# rpi-sstv.net
KiCad netlist of a schematic drawn in EAGLE
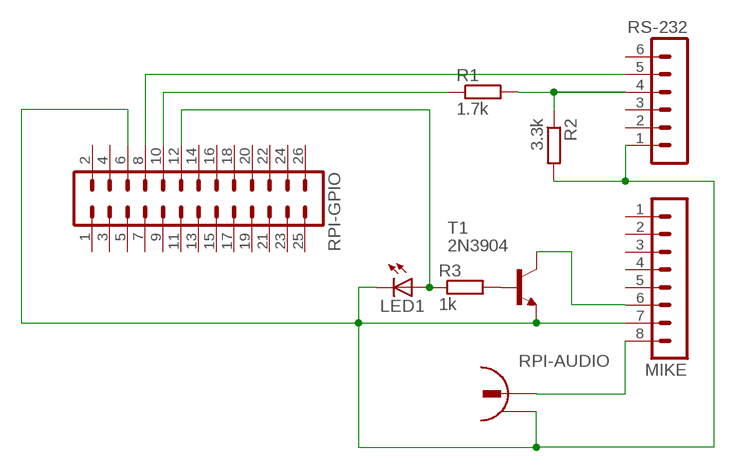
[diagram p0: schematic, sheet 1]

(export (version "E")
  (design (tool "Eeschema 10.0.6"))
  (components
    (comp (ref "LED1")
      (value "LED5MM")
      (footprint "eagle-import:LED5MM")
      (libsource (lib "eagle-import") (part "LED5MM"))
    )
    (comp (ref "MIKE")
      (value "MA08-1")
      (footprint "eagle-import:MA08-1")
      (libsource (lib "eagle-import") (part "MA08-1"))
    )
    (comp (ref "R1")
      (value "1.7k")
      (footprint "eagle-import:0411_15")
      (libsource (lib "eagle-import") (part "R-EU_0411/15"))
    )
    (comp (ref "R2")
      (value "3.3k")
      (footprint "eagle-import:0411_15")
      (libsource (lib "eagle-import") (part "R-EU_0411/15"))
    )
    (comp (ref "R3")
      (value "1k")
      (footprint "eagle-import:0411_15")
      (libsource (lib "eagle-import") (part "R-EU_0411/15"))
    )
    (comp (ref "RPI-AUDIO")
      (value "736880-49")
      (footprint "eagle-import:736880-49")
      (libsource (lib "eagle-import") (part "736880-49"))
    )
    (comp (ref "RPI-GPIO")
      (value "MA13-2")
      (footprint "eagle-import:MA13-2")
      (libsource (lib "eagle-import") (part "MA13-2"))
    )
    (comp (ref "RS-232")
      (value "MA06-1")
      (footprint "eagle-import:MA06-1")
      (libsource (lib "eagle-import") (part "MA06-1"))
    )
    (comp (ref "T1")
      (value "2N3904")
      (footprint "eagle-import:TO92")
      (libsource (lib "eagle-import") (part "2N3904"))
    )
  )
  (nets
    (net (code "1") (name "Net-(LED1-C)") (class "Default")
      (node (ref "LED1") (pin "K") (pinfunction "C_K") (pintype "passive"))
      (node (ref "MIKE") (pin "7") (pinfunction "7_7") (pintype "passive"))
      (node (ref "R2") (pin "2") (pinfunction "2_2") (pintype "passive"))
      (node (ref "RPI-AUDIO") (pin "2") (pinfunction "2_2") (pintype "passive"))
      (node (ref "RPI-GPIO") (pin "6") (pinfunction "6_6") (pintype "passive"))
      (node (ref "RS-232") (pin "1") (pinfunction "1_1") (pintype "passive"))
      (node (ref "T1") (pin "3") (pinfunction "E_3") (pintype "passive"))
    )
    (net (code "2") (name "Net-(LED1-PadA)") (class "Default")
      (node (ref "LED1") (pin "A") (pinfunction "A_A") (pintype "passive"))
      (node (ref "R3") (pin "1") (pinfunction "1_1") (pintype "passive"))
      (node (ref "RPI-GPIO") (pin "12") (pinfunction "12_12") (pintype "passive"))
    )
    (net (code "3") (name "Net-(MIKE-Pad8)") (class "Default")
      (node (ref "MIKE") (pin "8") (pinfunction "8_8") (pintype "passive"))
      (node (ref "RPI-AUDIO") (pin "1") (pinfunction "1_1") (pintype "passive"))
    )
    (net (code "4") (name "Net-(R1-Pad1)") (class "Default")
      (node (ref "R1") (pin "1") (pinfunction "1_1") (pintype "passive"))
      (node (ref "RPI-GPIO") (pin "10") (pinfunction "10_10") (pintype "passive"))
    )
    (net (code "5") (name "Net-(R1-Pad2)") (class "Default")
      (node (ref "R1") (pin "2") (pinfunction "2_2") (pintype "passive"))
      (node (ref "R2") (pin "1") (pinfunction "1_1") (pintype "passive"))
      (node (ref "RS-232") (pin "4") (pinfunction "4_4") (pintype "passive"))
    )
    (net (code "6") (name "Net-(RPI-GPIO-Pad8)") (class "Default")
      (node (ref "RPI-GPIO") (pin "8") (pinfunction "8_8") (pintype "passive"))
      (node (ref "RS-232") (pin "5") (pinfunction "5_5") (pintype "passive"))
    )
    (net (code "7") (name "Net-(T1-B)") (class "Default")
      (node (ref "R3") (pin "2") (pinfunction "2_2") (pintype "passive"))
      (node (ref "T1") (pin "2") (pinfunction "B_2") (pintype "passive"))
    )
    (net (code "8") (name "Net-(T1-C)") (class "Default")
      (node (ref "MIKE") (pin "6") (pinfunction "6_6") (pintype "passive"))
      (node (ref "T1") (pin "1") (pinfunction "C_1") (pintype "passive"))
    )
    (net (code "9") (name "unconnected-(MIKE-Pad1)") (class "Default")
      (node (ref "MIKE") (pin "1") (pinfunction "1_1") (pintype "passive"))
    )
    (net (code "10") (name "unconnected-(MIKE-Pad2)") (class "Default")
      (node (ref "MIKE") (pin "2") (pinfunction "2_2") (pintype "passive"))
    )
    (net (code "11") (name "unconnected-(MIKE-Pad3)") (class "Default")
      (node (ref "MIKE") (pin "3") (pinfunction "3_3") (pintype "passive"))
    )
    (net (code "12") (name "unconnected-(MIKE-Pad4)") (class "Default")
      (node (ref "MIKE") (pin "4") (pinfunction "4_4") (pintype "passive"))
    )
    (net (code "13") (name "unconnected-(MIKE-Pad5)") (class "Default")
      (node (ref "MIKE") (pin "5") (pinfunction "5_5") (pintype "passive"))
    )
    (net (code "14") (name "unconnected-(RPI-AUDIO-2-Pad2@2)") (class "Default")
      (node (ref "RPI-AUDIO") (pin "2@2") (pinfunction "2_2@2") (pintype "passive"))
    )
    (net (code "15") (name "unconnected-(RPI-GPIO-Pad1)") (class "Default")
      (node (ref "RPI-GPIO") (pin "1") (pinfunction "1_1") (pintype "passive"))
    )
    (net (code "16") (name "unconnected-(RPI-GPIO-Pad2)") (class "Default")
      (node (ref "RPI-GPIO") (pin "2") (pinfunction "2_2") (pintype "passive"))
    )
    (net (code "17") (name "unconnected-(RPI-GPIO-Pad3)") (class "Default")
      (node (ref "RPI-GPIO") (pin "3") (pinfunction "3_3") (pintype "passive"))
    )
    (net (code "18") (name "unconnected-(RPI-GPIO-Pad4)") (class "Default")
      (node (ref "RPI-GPIO") (pin "4") (pinfunction "4_4") (pintype "passive"))
    )
    (net (code "19") (name "unconnected-(RPI-GPIO-Pad5)") (class "Default")
      (node (ref "RPI-GPIO") (pin "5") (pinfunction "5_5") (pintype "passive"))
    )
    (net (code "20") (name "unconnected-(RPI-GPIO-Pad7)") (class "Default")
      (node (ref "RPI-GPIO") (pin "7") (pinfunction "7_7") (pintype "passive"))
    )
    (net (code "21") (name "unconnected-(RPI-GPIO-Pad9)") (class "Default")
      (node (ref "RPI-GPIO") (pin "9") (pinfunction "9_9") (pintype "passive"))
    )
    (net (code "22") (name "unconnected-(RPI-GPIO-Pad11)") (class "Default")
      (node (ref "RPI-GPIO") (pin "11") (pinfunction "11_11") (pintype "passive"))
    )
    (net (code "23") (name "unconnected-(RPI-GPIO-Pad13)") (class "Default")
      (node (ref "RPI-GPIO") (pin "13") (pinfunction "13_13") (pintype "passive"))
    )
    (net (code "24") (name "unconnected-(RPI-GPIO-Pad14)") (class "Default")
      (node (ref "RPI-GPIO") (pin "14") (pinfunction "14_14") (pintype "passive"))
    )
    (net (code "25") (name "unconnected-(RPI-GPIO-Pad15)") (class "Default")
      (node (ref "RPI-GPIO") (pin "15") (pinfunction "15_15") (pintype "passive"))
    )
    (net (code "26") (name "unconnected-(RPI-GPIO-Pad16)") (class "Default")
      (node (ref "RPI-GPIO") (pin "16") (pinfunction "16_16") (pintype "passive"))
    )
    (net (code "27") (name "unconnected-(RPI-GPIO-Pad17)") (class "Default")
      (node (ref "RPI-GPIO") (pin "17") (pinfunction "17_17") (pintype "passive"))
    )
    (net (code "28") (name "unconnected-(RPI-GPIO-Pad18)") (class "Default")
      (node (ref "RPI-GPIO") (pin "18") (pinfunction "18_18") (pintype "passive"))
    )
    (net (code "29") (name "unconnected-(RPI-GPIO-Pad19)") (class "Default")
      (node (ref "RPI-GPIO") (pin "19") (pinfunction "19_19") (pintype "passive"))
    )
    (net (code "30") (name "unconnected-(RPI-GPIO-Pad20)") (class "Default")
      (node (ref "RPI-GPIO") (pin "20") (pinfunction "20_20") (pintype "passive"))
    )
    (net (code "31") (name "unconnected-(RPI-GPIO-Pad21)") (class "Default")
      (node (ref "RPI-GPIO") (pin "21") (pinfunction "21_21") (pintype "passive"))
    )
    (net (code "32") (name "unconnected-(RPI-GPIO-Pad22)") (class "Default")
      (node (ref "RPI-GPIO") (pin "22") (pinfunction "22_22") (pintype "passive"))
    )
    (net (code "33") (name "unconnected-(RPI-GPIO-Pad23)") (class "Default")
      (node (ref "RPI-GPIO") (pin "23") (pinfunction "23_23") (pintype "passive"))
    )
    (net (code "34") (name "unconnected-(RPI-GPIO-Pad24)") (class "Default")
      (node (ref "RPI-GPIO") (pin "24") (pinfunction "24_24") (pintype "passive"))
    )
    (net (code "35") (name "unconnected-(RPI-GPIO-Pad25)") (class "Default")
      (node (ref "RPI-GPIO") (pin "25") (pinfunction "25_25") (pintype "passive"))
    )
    (net (code "36") (name "unconnected-(RPI-GPIO-Pad26)") (class "Default")
      (node (ref "RPI-GPIO") (pin "26") (pinfunction "26_26") (pintype "passive"))
    )
    (net (code "37") (name "unconnected-(RS-232-Pad2)") (class "Default")
      (node (ref "RS-232") (pin "2") (pinfunction "2_2") (pintype "passive"))
    )
    (net (code "38") (name "unconnected-(RS-232-Pad3)") (class "Default")
      (node (ref "RS-232") (pin "3") (pinfunction "3_3") (pintype "passive"))
    )
    (net (code "39") (name "unconnected-(RS-232-Pad6)") (class "Default")
      (node (ref "RS-232") (pin "6") (pinfunction "6_6") (pintype "passive"))
    )
  )
)
